# BMX160.net
KiCad netlist of a schematic drawn in Altium Designer
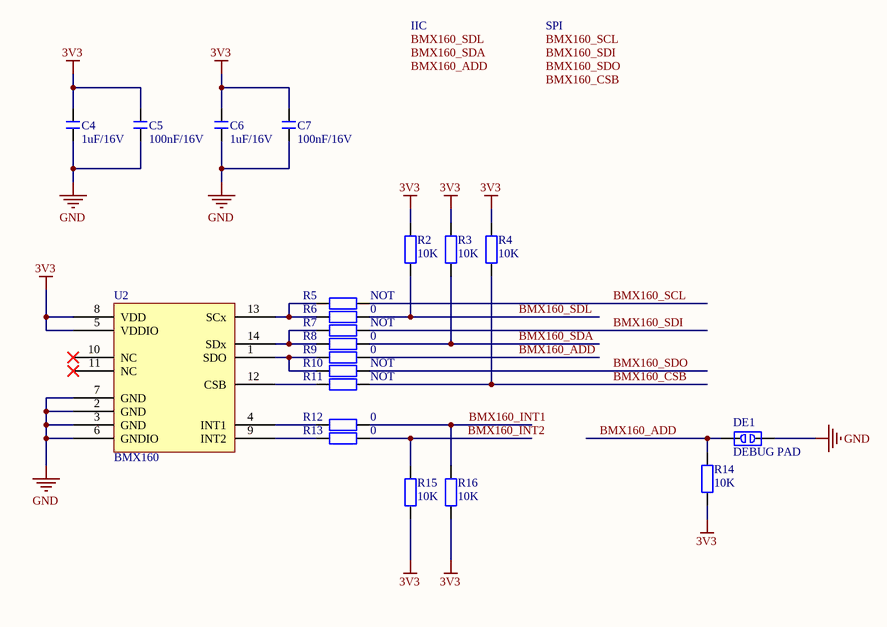
[diagram p0: BMX160.SchDoc]

(export (version "E")
  (design (tool "Eeschema 10.0.6"))
  (components
    (comp (ref "C4")
      (value "1uF/16V")
      (footprint "C 0402_L")
      (description "贴片电容")
      (libsource (lib "3.1   - 电阻-电容-电感") (part "C"))
    )
    (comp (ref "C5")
      (value "100nF/16V")
      (footprint "C 0402_L")
      (description "无极性贴片电容")
      (libsource (lib "3.1   - 电阻-电容-电感") (part "C"))
    )
    (comp (ref "C6")
      (value "1uF/16V")
      (footprint "C 0402_L")
      (description "贴片电容")
      (libsource (lib "3.1   - 电阻-电容-电感") (part "C"))
    )
    (comp (ref "C7")
      (value "100nF/16V")
      (footprint "C 0402_L")
      (description "无极性贴片电容")
      (libsource (lib "3.1   - 电阻-电容-电感") (part "C"))
    )
    (comp (ref "DE1")
      (value "DEBUG PAD")
      (footprint "DEBUG_A")
      (description "调试断点焊盘")
      (fields (field (name "版权归属") "源创客"))
      (libsource (lib "15.1 - 未分类器件") (part "DEBUG"))
    )
    (comp (ref "R2")
      (value "10K")
      (footprint "R 0402_L")
      (description "贴片电阻 0402 1%")
      (libsource (lib "3.1   - 电阻-电容-电感") (part "R"))
    )
    (comp (ref "R3")
      (value "10K")
      (footprint "R 0402_L")
      (description "贴片电阻 0402 1%")
      (libsource (lib "3.1   - 电阻-电容-电感") (part "R"))
    )
    (comp (ref "R4")
      (value "10K")
      (footprint "R 0402_L")
      (description "贴片电阻 0402 1%")
      (libsource (lib "3.1   - 电阻-电容-电感") (part "R"))
    )
    (comp (ref "R5")
      (value "NOT")
      (footprint "R 0402_L")
      (description "贴片电阻")
      (libsource (lib "3.1   - 电阻-电容-电感") (part "R"))
    )
    (comp (ref "R6")
      (value "0")
      (footprint "R 0402_L")
      (description "贴片电阻")
      (libsource (lib "3.1   - 电阻-电容-电感") (part "R"))
    )
    (comp (ref "R7")
      (value "NOT")
      (footprint "R 0402_L")
      (description "贴片电阻")
      (libsource (lib "3.1   - 电阻-电容-电感") (part "R"))
    )
    (comp (ref "R8")
      (value "0")
      (footprint "R 0402_L")
      (description "贴片电阻")
      (libsource (lib "3.1   - 电阻-电容-电感") (part "R"))
    )
    (comp (ref "R9")
      (value "0")
      (footprint "R 0402_L")
      (description "贴片电阻")
      (libsource (lib "3.1   - 电阻-电容-电感") (part "R"))
    )
    (comp (ref "R10")
      (value "NOT")
      (footprint "R 0402_L")
      (description "贴片电阻")
      (libsource (lib "3.1   - 电阻-电容-电感") (part "R"))
    )
    (comp (ref "R11")
      (value "NOT")
      (footprint "R 0402_L")
      (description "贴片电阻")
      (libsource (lib "3.1   - 电阻-电容-电感") (part "R"))
    )
    (comp (ref "R12")
      (value "0")
      (footprint "R 0402_L")
      (description "贴片电阻")
      (libsource (lib "3.1   - 电阻-电容-电感") (part "R"))
    )
    (comp (ref "R13")
      (value "0")
      (footprint "R 0402_L")
      (description "贴片电阻")
      (libsource (lib "3.1   - 电阻-电容-电感") (part "R"))
    )
    (comp (ref "R14")
      (value "10K")
      (footprint "R 0402_L")
      (description "贴片电阻 0402 1%")
      (libsource (lib "3.1   - 电阻-电容-电感") (part "R"))
    )
    (comp (ref "R15")
      (value "10K")
      (footprint "R 0402_L")
      (description "贴片电阻 0402 1%")
      (libsource (lib "3.1   - 电阻-电容-电感") (part "R"))
    )
    (comp (ref "R16")
      (value "10K")
      (footprint "R 0402_L")
      (description "贴片电阻 0402 1%")
      (libsource (lib "3.1   - 电阻-电容-电感") (part "R"))
    )
    (comp (ref "U2") (value "BMX160") (footprint "BMX160") (libsource (lib "Schlib1") (part "BMX160")))
  )
  (nets
    (net (code "1") (name "/BMX160_ADD") (class "Default")
      (node (ref "DE1") (pin "1") (pinfunction "1_1") (pintype "passive"))
      (node (ref "R14") (pin "2") (pinfunction "2_2") (pintype "passive"))
      (node (ref "R9") (pin "1") (pinfunction "1_1") (pintype "passive"))
    )
    (net (code "2") (name "/BMX160_CSB") (class "Default")
      (node (ref "R11") (pin "1") (pinfunction "1_1") (pintype "passive"))
      (node (ref "R4") (pin "2") (pinfunction "2_2") (pintype "passive"))
    )
    (net (code "3") (name "/BMX160_INT1") (class "Default")
      (node (ref "R12") (pin "1") (pinfunction "1_1") (pintype "passive"))
      (node (ref "R16") (pin "2") (pinfunction "2_2") (pintype "passive"))
    )
    (net (code "4") (name "/BMX160_INT2") (class "Default")
      (node (ref "R13") (pin "1") (pinfunction "1_1") (pintype "passive"))
      (node (ref "R15") (pin "2") (pinfunction "2_2") (pintype "passive"))
    )
    (net (code "5") (name "/BMX160_SCL") (class "Default")
      (node (ref "R5") (pin "1") (pinfunction "1_1") (pintype "passive"))
    )
    (net (code "6") (name "/BMX160_SDA") (class "Default")
      (node (ref "R3") (pin "2") (pinfunction "2_2") (pintype "passive"))
      (node (ref "R8") (pin "1") (pinfunction "1_1") (pintype "passive"))
    )
    (net (code "7") (name "/BMX160_SDI") (class "Default")
      (node (ref "R7") (pin "1") (pinfunction "1_1") (pintype "passive"))
    )
    (net (code "8") (name "/BMX160_SDL") (class "Default")
      (node (ref "R2") (pin "2") (pinfunction "2_2") (pintype "passive"))
      (node (ref "R6") (pin "1") (pinfunction "1_1") (pintype "passive"))
    )
    (net (code "9") (name "/BMX160_SDO") (class "Default")
      (node (ref "R10") (pin "1") (pinfunction "1_1") (pintype "passive"))
    )
    (net (code "10") (name "3V3") (class "Default")
      (node (ref "C4") (pin "2") (pinfunction "2_2") (pintype "passive"))
      (node (ref "C5") (pin "1") (pinfunction "1_1") (pintype "passive"))
      (node (ref "C6") (pin "2") (pinfunction "2_2") (pintype "passive"))
      (node (ref "C7") (pin "1") (pinfunction "1_1") (pintype "passive"))
      (node (ref "R14") (pin "1") (pinfunction "1_1") (pintype "passive"))
      (node (ref "R15") (pin "1") (pinfunction "1_1") (pintype "passive"))
      (node (ref "R16") (pin "1") (pinfunction "1_1") (pintype "passive"))
      (node (ref "R2") (pin "1") (pinfunction "1_1") (pintype "passive"))
      (node (ref "R3") (pin "1") (pinfunction "1_1") (pintype "passive"))
      (node (ref "R4") (pin "1") (pinfunction "1_1") (pintype "passive"))
      (node (ref "U2") (pin "5") (pinfunction "VDDIO_5") (pintype "passive"))
      (node (ref "U2") (pin "8") (pinfunction "VDD_8") (pintype "passive"))
    )
    (net (code "11") (name "GND") (class "Default")
      (node (ref "C4") (pin "1") (pinfunction "1_1") (pintype "passive"))
      (node (ref "C5") (pin "2") (pinfunction "2_2") (pintype "passive"))
      (node (ref "C6") (pin "1") (pinfunction "1_1") (pintype "passive"))
      (node (ref "C7") (pin "2") (pinfunction "2_2") (pintype "passive"))
      (node (ref "DE1") (pin "2") (pinfunction "2_2") (pintype "passive"))
      (node (ref "U2") (pin "2") (pinfunction "GND_2") (pintype "passive"))
      (node (ref "U2") (pin "3") (pinfunction "GND_3") (pintype "passive"))
      (node (ref "U2") (pin "6") (pinfunction "GNDIO_6") (pintype "passive"))
      (node (ref "U2") (pin "7") (pinfunction "GND_7") (pintype "passive"))
    )
    (net (code "12") (name "Net-(U2-CSB)") (class "Default")
      (node (ref "R11") (pin "2") (pinfunction "2_2") (pintype "passive"))
      (node (ref "U2") (pin "12") (pinfunction "CSB_12") (pintype "passive"))
    )
    (net (code "13") (name "Net-(U2-INT1)") (class "Default")
      (node (ref "R12") (pin "2") (pinfunction "2_2") (pintype "passive"))
      (node (ref "U2") (pin "4") (pinfunction "INT1_4") (pintype "passive"))
    )
    (net (code "14") (name "Net-(U2-INT2)") (class "Default")
      (node (ref "R13") (pin "2") (pinfunction "2_2") (pintype "passive"))
      (node (ref "U2") (pin "9") (pinfunction "INT2_9") (pintype "passive"))
    )
    (net (code "15") (name "Net-(U2-SCx)") (class "Default")
      (node (ref "R5") (pin "2") (pinfunction "2_2") (pintype "passive"))
      (node (ref "R6") (pin "2") (pinfunction "2_2") (pintype "passive"))
      (node (ref "U2") (pin "13") (pinfunction "SCx_13") (pintype "passive"))
    )
    (net (code "16") (name "Net-(U2-SDO)") (class "Default")
      (node (ref "R10") (pin "2") (pinfunction "2_2") (pintype "passive"))
      (node (ref "R9") (pin "2") (pinfunction "2_2") (pintype "passive"))
      (node (ref "U2") (pin "1") (pinfunction "SDO_1") (pintype "passive"))
    )
    (net (code "17") (name "Net-(U2-SDx)") (class "Default")
      (node (ref "R7") (pin "2") (pinfunction "2_2") (pintype "passive"))
      (node (ref "R8") (pin "2") (pinfunction "2_2") (pintype "passive"))
      (node (ref "U2") (pin "14") (pinfunction "SDx_14") (pintype "passive"))
    )
    (net (code "18") (name "unconnected-(U2-NC-Pad10)") (class "Default")
      (node (ref "U2") (pin "10") (pinfunction "NC_10") (pintype "passive+no_connect"))
    )
    (net (code "19") (name "unconnected-(U2-NC-Pad11)") (class "Default")
      (node (ref "U2") (pin "11") (pinfunction "NC_11") (pintype "passive+no_connect"))
    )
  )
)
